# tweeq-IB_Protoboard_v3.net
KiCad netlist of a schematic drawn in EAGLE
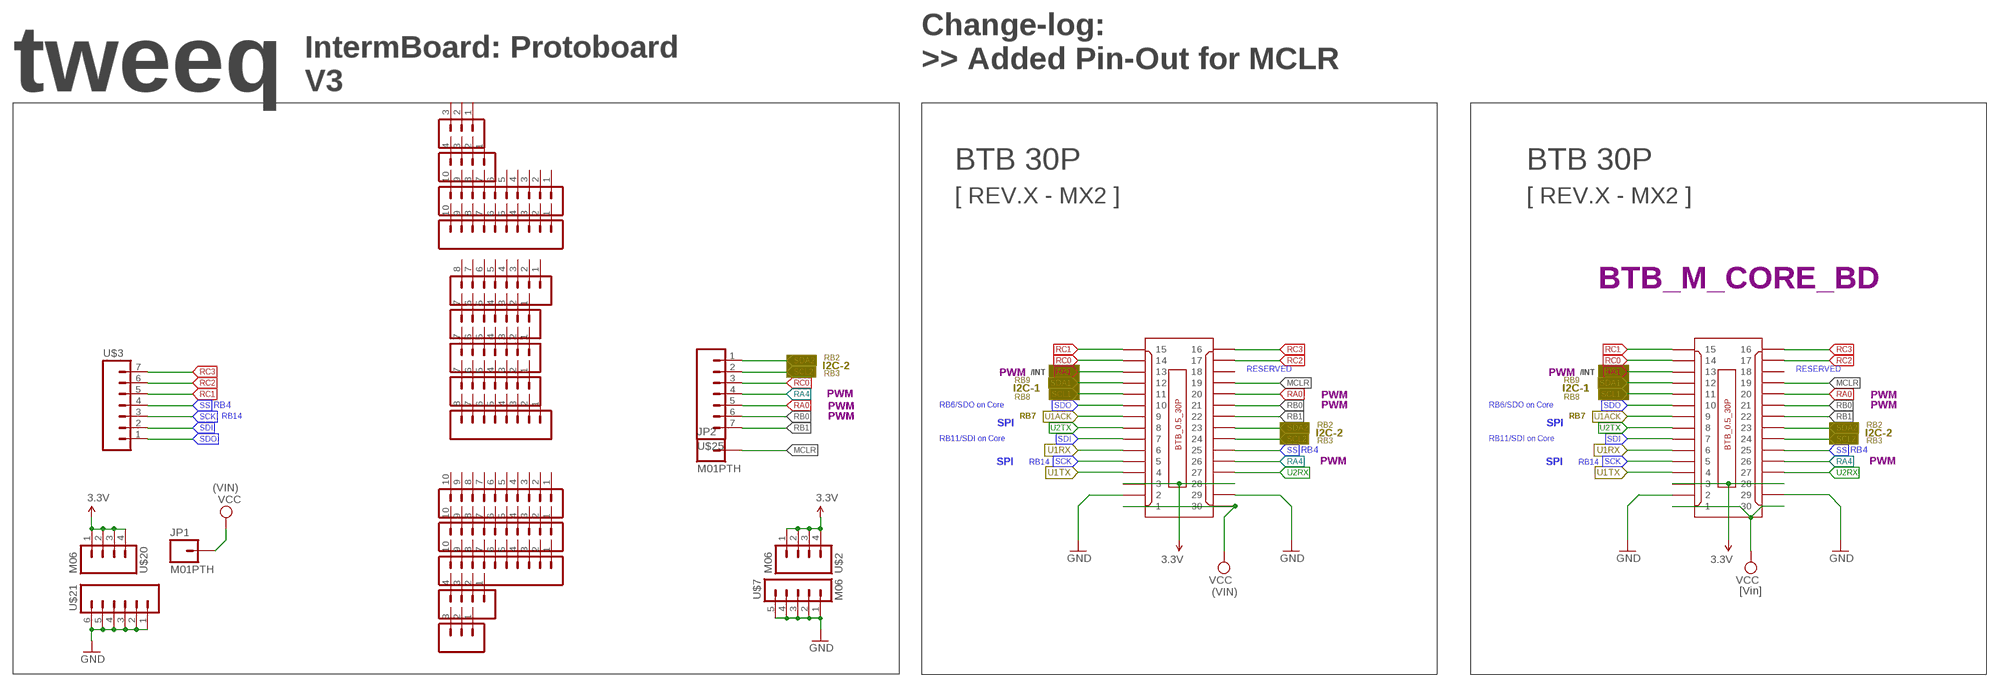
[diagram p0: schematic, sheet 1]

(export (version "E")
  (design (tool "Eeschema 10.0.6"))
  (components
    (comp (ref "JP1")
      (value "M01PTH")
      (footprint "eagle-import:1X01")
      (libsource (lib "eagle-import") (part "M01PTH"))
    )
    (comp (ref "JP2")
      (value "M01PTH")
      (footprint "eagle-import:1X01")
      (libsource (lib "eagle-import") (part "M01PTH"))
    )
    (comp (ref "U$2")
      (value "M06")
      (footprint "eagle-import:1X04_NS_ROUND")
      (libsource (lib "eagle-import") (part "M04NS-CIRC"))
    )
    (comp (ref "U$3")
      (value "M072.54NOSILK")
      (footprint "eagle-import:1X07_NOSILK_")
      (libsource (lib "eagle-import") (part "M072.54NOSILK"))
    )
    (comp (ref "U$4")
      (value "BTB_CONN_30P/F")
      (footprint "eagle-import:BTB0.5-30F-3.0G")
      (libsource (lib "eagle-import") (part "BTB_CONN_30P/F"))
    )
    (comp (ref "U$5")
      (value "M10-1/NS-SQ")
      (footprint "eagle-import:1X03-NS-SQ")
      (libsource (lib "eagle-import") (part "M03NS-SQ"))
    )
    (comp (ref "U$7")
      (value "M06")
      (footprint "eagle-import:1X05-NS-SQ")
      (libsource (lib "eagle-import") (part "M05-1NS-SQ"))
    )
    (comp (ref "U$8")
      (value "M09")
      (footprint "eagle-import:1X10-NS-SQ")
      (libsource (lib "eagle-import") (part "M10-1/NS-SQ"))
    )
    (comp (ref "U$9")
      (value "M09")
      (footprint "eagle-import:1X08-NS-SQ")
      (libsource (lib "eagle-import") (part "M08-1/NS-SQ"))
    )
    (comp (ref "U$10")
      (value "M09")
      (footprint "eagle-import:1X07-NS-SQ")
      (libsource (lib "eagle-import") (part "M07/NS-SQ"))
    )
    (comp (ref "U$11")
      (value "M09")
      (footprint "eagle-import:1X07-NS-SQ")
      (libsource (lib "eagle-import") (part "M07/NS-SQ"))
    )
    (comp (ref "U$12")
      (value "M09")
      (footprint "eagle-import:1X07-NS-SQ")
      (libsource (lib "eagle-import") (part "M07/NS-SQ"))
    )
    (comp (ref "U$13")
      (value "M10-10.1")
      (footprint "eagle-import:1X08-NS-SQ")
      (libsource (lib "eagle-import") (part "M08-1/NS-SQ"))
    )
    (comp (ref "U$14")
      (value "M10-1/NS-SQ")
      (footprint "eagle-import:1X10-NS-SQ")
      (libsource (lib "eagle-import") (part "M10-1/NS-SQ"))
    )
    (comp (ref "U$15")
      (value "M10-1/NS-SQ")
      (footprint "eagle-import:1X10-NS-SQ")
      (libsource (lib "eagle-import") (part "M10-1/NS-SQ"))
    )
    (comp (ref "U$16")
      (value "M10-1/NS-SQ")
      (footprint "eagle-import:1X10-NS-SQ")
      (libsource (lib "eagle-import") (part "M10-1/NS-SQ"))
    )
    (comp (ref "U$17")
      (value "M10-1/NS-SQ")
      (footprint "eagle-import:1X04-NS-SQ")
      (libsource (lib "eagle-import") (part "M04NS-SQ"))
    )
    (comp (ref "U$18")
      (value "M10-1/NS-SQ")
      (footprint "eagle-import:1X10-NS-SQ")
      (libsource (lib "eagle-import") (part "M10-1/NS-SQ"))
    )
    (comp (ref "U$19")
      (value "M10-1/NS-SQ")
      (footprint "eagle-import:1X03-NS-SQ")
      (libsource (lib "eagle-import") (part "M03NS-SQ"))
    )
    (comp (ref "U$20")
      (value "M06")
      (footprint "eagle-import:1X04_NS_ROUND")
      (libsource (lib "eagle-import") (part "M04NS-CIRC"))
    )
    (comp (ref "U$21")
      (value "M06NS-SQ")
      (footprint "eagle-import:1X06-NS-SQ")
      (libsource (lib "eagle-import") (part "M06NS-SQ"))
    )
    (comp (ref "U$22")
      (value "BTB_CONN_30P/M")
      (footprint "eagle-import:BTB0.5-30M-3.0G")
      (libsource (lib "eagle-import") (part "BTB_CONN_30P/M"))
    )
    (comp (ref "U$23")
      (value "M10-1/NS-SQ")
      (footprint "eagle-import:1X04-NS-SQ")
      (libsource (lib "eagle-import") (part "M04NS-SQ"))
    )
    (comp (ref "U$25")
      (value "M072.54NOSILK")
      (footprint "eagle-import:1X07_NOSILK_")
      (libsource (lib "eagle-import") (part "M072.54NOSILK"))
    )
  )
  (nets
    (net (code "1") (name "3.3V") (class "Default")
      (node (ref "U$2") (pin "1") (pinfunction "1_1") (pintype "passive"))
      (node (ref "U$2") (pin "2") (pinfunction "2_2") (pintype "passive"))
      (node (ref "U$2") (pin "3") (pinfunction "3_3") (pintype "passive"))
      (node (ref "U$2") (pin "4") (pinfunction "4_4") (pintype "passive"))
      (node (ref "U$20") (pin "1") (pinfunction "1_1") (pintype "passive"))
      (node (ref "U$20") (pin "2") (pinfunction "2_2") (pintype "passive"))
      (node (ref "U$20") (pin "3") (pinfunction "3_3") (pintype "passive"))
      (node (ref "U$20") (pin "4") (pinfunction "4_4") (pintype "passive"))
      (node (ref "U$22") (pin "28") (pinfunction "28_28") (pintype "bidirectional"))
      (node (ref "U$22") (pin "3") (pinfunction "3_3") (pintype "bidirectional"))
      (node (ref "U$4") (pin "28") (pinfunction "28_28") (pintype "bidirectional"))
      (node (ref "U$4") (pin "3") (pinfunction "3_3") (pintype "bidirectional"))
    )
    (net (code "2") (name "GND") (class "Default")
      (node (ref "U$21") (pin "1") (pinfunction "1_1") (pintype "passive"))
      (node (ref "U$21") (pin "2") (pinfunction "2_2") (pintype "passive"))
      (node (ref "U$21") (pin "3") (pinfunction "3_3") (pintype "passive"))
      (node (ref "U$21") (pin "4") (pinfunction "4_4") (pintype "passive"))
      (node (ref "U$21") (pin "5") (pinfunction "5_5") (pintype "passive"))
      (node (ref "U$21") (pin "6") (pinfunction "6_6") (pintype "passive"))
      (node (ref "U$22") (pin "2") (pinfunction "2_2") (pintype "bidirectional"))
      (node (ref "U$22") (pin "29") (pinfunction "29_29") (pintype "bidirectional"))
      (node (ref "U$4") (pin "2") (pinfunction "2_2") (pintype "bidirectional"))
      (node (ref "U$4") (pin "29") (pinfunction "29_29") (pintype "bidirectional"))
      (node (ref "U$7") (pin "1") (pinfunction "1_1") (pintype "passive"))
      (node (ref "U$7") (pin "2") (pinfunction "2_2") (pintype "passive"))
      (node (ref "U$7") (pin "3") (pinfunction "3_3") (pintype "passive"))
      (node (ref "U$7") (pin "4") (pinfunction "4_4") (pintype "passive"))
      (node (ref "U$7") (pin "5") (pinfunction "5_5") (pintype "passive"))
    )
    (net (code "3") (name "MCLR") (class "Default")
      (node (ref "JP2") (pin "1") (pinfunction "1_1") (pintype "passive"))
      (node (ref "U$22") (pin "19") (pinfunction "19_19") (pintype "bidirectional"))
      (node (ref "U$4") (pin "19") (pinfunction "19_19") (pintype "bidirectional"))
    )
    (net (code "4") (name "RA0") (class "Default")
      (node (ref "U$22") (pin "20") (pinfunction "20_20") (pintype "bidirectional"))
      (node (ref "U$25") (pin "5") (pinfunction "5_5") (pintype "passive"))
      (node (ref "U$4") (pin "20") (pinfunction "20_20") (pintype "bidirectional"))
    )
    (net (code "5") (name "RA1") (class "Default")
      (node (ref "U$22") (pin "13") (pinfunction "13_13") (pintype "bidirectional"))
      (node (ref "U$4") (pin "13") (pinfunction "13_13") (pintype "bidirectional"))
    )
    (net (code "6") (name "RA4") (class "Default")
      (node (ref "U$22") (pin "26") (pinfunction "26_26") (pintype "bidirectional"))
      (node (ref "U$25") (pin "4") (pinfunction "4_4") (pintype "passive"))
      (node (ref "U$4") (pin "26") (pinfunction "26_26") (pintype "bidirectional"))
    )
    (net (code "7") (name "RB0") (class "Default")
      (node (ref "U$22") (pin "21") (pinfunction "21_21") (pintype "bidirectional"))
      (node (ref "U$25") (pin "6") (pinfunction "6_6") (pintype "passive"))
      (node (ref "U$4") (pin "21") (pinfunction "21_21") (pintype "bidirectional"))
    )
    (net (code "8") (name "RB1") (class "Default")
      (node (ref "U$22") (pin "22") (pinfunction "22_22") (pintype "bidirectional"))
      (node (ref "U$25") (pin "7") (pinfunction "7_7") (pintype "passive"))
      (node (ref "U$4") (pin "22") (pinfunction "22_22") (pintype "bidirectional"))
    )
    (net (code "9") (name "RC0") (class "Default")
      (node (ref "U$22") (pin "14") (pinfunction "14_14") (pintype "bidirectional"))
      (node (ref "U$25") (pin "3") (pinfunction "3_3") (pintype "passive"))
      (node (ref "U$4") (pin "14") (pinfunction "14_14") (pintype "bidirectional"))
    )
    (net (code "10") (name "RC1") (class "Default")
      (node (ref "U$22") (pin "15") (pinfunction "15_15") (pintype "bidirectional"))
      (node (ref "U$3") (pin "5") (pinfunction "5_5") (pintype "passive"))
      (node (ref "U$4") (pin "15") (pinfunction "15_15") (pintype "bidirectional"))
    )
    (net (code "11") (name "RC2") (class "Default")
      (node (ref "U$22") (pin "17") (pinfunction "17_17") (pintype "bidirectional"))
      (node (ref "U$3") (pin "6") (pinfunction "6_6") (pintype "passive"))
      (node (ref "U$4") (pin "17") (pinfunction "17_17") (pintype "bidirectional"))
    )
    (net (code "12") (name "RC3") (class "Default")
      (node (ref "U$22") (pin "16") (pinfunction "16_16") (pintype "bidirectional"))
      (node (ref "U$3") (pin "7") (pinfunction "7_7") (pintype "passive"))
      (node (ref "U$4") (pin "16") (pinfunction "16_16") (pintype "bidirectional"))
    )
    (net (code "13") (name "SCK") (class "Default")
      (node (ref "U$22") (pin "5") (pinfunction "5_5") (pintype "bidirectional"))
      (node (ref "U$3") (pin "3") (pinfunction "3_3") (pintype "passive"))
      (node (ref "U$4") (pin "5") (pinfunction "5_5") (pintype "bidirectional"))
    )
    (net (code "14") (name "SCL1") (class "Default")
      (node (ref "U$22") (pin "11") (pinfunction "11_11") (pintype "bidirectional"))
      (node (ref "U$4") (pin "11") (pinfunction "11_11") (pintype "bidirectional"))
    )
    (net (code "15") (name "SCL2") (class "Default")
      (node (ref "U$22") (pin "24") (pinfunction "24_24") (pintype "bidirectional"))
      (node (ref "U$25") (pin "2") (pinfunction "2_2") (pintype "passive"))
      (node (ref "U$4") (pin "24") (pinfunction "24_24") (pintype "bidirectional"))
    )
    (net (code "16") (name "SDA1") (class "Default")
      (node (ref "U$22") (pin "12") (pinfunction "12_12") (pintype "bidirectional"))
      (node (ref "U$4") (pin "12") (pinfunction "12_12") (pintype "bidirectional"))
    )
    (net (code "17") (name "SDA2") (class "Default")
      (node (ref "U$22") (pin "23") (pinfunction "23_23") (pintype "bidirectional"))
      (node (ref "U$25") (pin "1") (pinfunction "1_1") (pintype "passive"))
      (node (ref "U$4") (pin "23") (pinfunction "23_23") (pintype "bidirectional"))
    )
    (net (code "18") (name "SDI") (class "Default")
      (node (ref "U$22") (pin "7") (pinfunction "7_7") (pintype "bidirectional"))
      (node (ref "U$3") (pin "2") (pinfunction "2_2") (pintype "passive"))
      (node (ref "U$4") (pin "7") (pinfunction "7_7") (pintype "bidirectional"))
    )
    (net (code "19") (name "SDO") (class "Default")
      (node (ref "U$22") (pin "10") (pinfunction "10_10") (pintype "bidirectional"))
      (node (ref "U$3") (pin "1") (pinfunction "1_1") (pintype "passive"))
      (node (ref "U$4") (pin "10") (pinfunction "10_10") (pintype "bidirectional"))
    )
    (net (code "20") (name "SS") (class "Default")
      (node (ref "U$22") (pin "25") (pinfunction "25_25") (pintype "bidirectional"))
      (node (ref "U$3") (pin "4") (pinfunction "4_4") (pintype "passive"))
      (node (ref "U$4") (pin "25") (pinfunction "25_25") (pintype "bidirectional"))
    )
    (net (code "21") (name "U1ACK") (class "Default")
      (node (ref "U$22") (pin "9") (pinfunction "9_9") (pintype "bidirectional"))
      (node (ref "U$4") (pin "9") (pinfunction "9_9") (pintype "bidirectional"))
    )
    (net (code "22") (name "U1RX") (class "Default")
      (node (ref "U$22") (pin "6") (pinfunction "6_6") (pintype "bidirectional"))
      (node (ref "U$4") (pin "6") (pinfunction "6_6") (pintype "bidirectional"))
    )
    (net (code "23") (name "U1TX") (class "Default")
      (node (ref "U$22") (pin "4") (pinfunction "4_4") (pintype "bidirectional"))
      (node (ref "U$4") (pin "4") (pinfunction "4_4") (pintype "bidirectional"))
    )
    (net (code "24") (name "U2RX") (class "Default")
      (node (ref "U$22") (pin "27") (pinfunction "27_27") (pintype "bidirectional"))
      (node (ref "U$4") (pin "27") (pinfunction "27_27") (pintype "bidirectional"))
    )
    (net (code "25") (name "U2TX") (class "Default")
      (node (ref "U$22") (pin "8") (pinfunction "8_8") (pintype "bidirectional"))
      (node (ref "U$4") (pin "8") (pinfunction "8_8") (pintype "bidirectional"))
    )
    (net (code "26") (name "VCC") (class "Default")
      (node (ref "JP1") (pin "1") (pinfunction "1_1") (pintype "passive"))
      (node (ref "U$22") (pin "1") (pinfunction "1_1") (pintype "bidirectional"))
      (node (ref "U$22") (pin "30") (pinfunction "30_30") (pintype "bidirectional"))
      (node (ref "U$4") (pin "1") (pinfunction "1_1") (pintype "bidirectional"))
      (node (ref "U$4") (pin "30") (pinfunction "30_30") (pintype "bidirectional"))
    )
    (net (code "27") (name "unconnected-(U$4-Pad18)") (class "Default")
      (node (ref "U$4") (pin "18") (pinfunction "18_18") (pintype "bidirectional"))
    )
    (net (code "28") (name "unconnected-(U$5-Pad1)") (class "Default")
      (node (ref "U$5") (pin "1") (pinfunction "1_1") (pintype "passive"))
    )
    (net (code "29") (name "unconnected-(U$5-Pad2)") (class "Default")
      (node (ref "U$5") (pin "2") (pinfunction "2_2") (pintype "passive"))
    )
    (net (code "30") (name "unconnected-(U$5-Pad3)") (class "Default")
      (node (ref "U$5") (pin "3") (pinfunction "3_3") (pintype "passive"))
    )
    (net (code "31") (name "unconnected-(U$8-Pad1)") (class "Default")
      (node (ref "U$8") (pin "1") (pinfunction "1_1") (pintype "passive"))
    )
    (net (code "32") (name "unconnected-(U$8-Pad2)") (class "Default")
      (node (ref "U$8") (pin "2") (pinfunction "2_2") (pintype "passive"))
    )
    (net (code "33") (name "unconnected-(U$8-Pad3)") (class "Default")
      (node (ref "U$8") (pin "3") (pinfunction "3_3") (pintype "passive"))
    )
    (net (code "34") (name "unconnected-(U$8-Pad4)") (class "Default")
      (node (ref "U$8") (pin "4") (pinfunction "4_4") (pintype "passive"))
    )
    (net (code "35") (name "unconnected-(U$8-Pad5)") (class "Default")
      (node (ref "U$8") (pin "5") (pinfunction "5_5") (pintype "passive"))
    )
    (net (code "36") (name "unconnected-(U$8-Pad6)") (class "Default")
      (node (ref "U$8") (pin "6") (pinfunction "6_6") (pintype "passive"))
    )
    (net (code "37") (name "unconnected-(U$8-Pad7)") (class "Default")
      (node (ref "U$8") (pin "7") (pinfunction "7_7") (pintype "passive"))
    )
    (net (code "38") (name "unconnected-(U$8-Pad8)") (class "Default")
      (node (ref "U$8") (pin "8") (pinfunction "8_8") (pintype "passive"))
    )
    (net (code "39") (name "unconnected-(U$8-Pad9)") (class "Default")
      (node (ref "U$8") (pin "9") (pinfunction "9_9") (pintype "passive"))
    )
    (net (code "40") (name "unconnected-(U$8-Pad10)") (class "Default")
      (node (ref "U$8") (pin "10") (pinfunction "10_10") (pintype "passive"))
    )
    (net (code "41") (name "unconnected-(U$9-Pad1)") (class "Default")
      (node (ref "U$9") (pin "1") (pinfunction "1_1") (pintype "passive"))
    )
    (net (code "42") (name "unconnected-(U$9-Pad2)") (class "Default")
      (node (ref "U$9") (pin "2") (pinfunction "2_2") (pintype "passive"))
    )
    (net (code "43") (name "unconnected-(U$9-Pad3)") (class "Default")
      (node (ref "U$9") (pin "3") (pinfunction "3_3") (pintype "passive"))
    )
    (net (code "44") (name "unconnected-(U$9-Pad4)") (class "Default")
      (node (ref "U$9") (pin "4") (pinfunction "4_4") (pintype "passive"))
    )
    (net (code "45") (name "unconnected-(U$9-Pad5)") (class "Default")
      (node (ref "U$9") (pin "5") (pinfunction "5_5") (pintype "passive"))
    )
    (net (code "46") (name "unconnected-(U$9-Pad6)") (class "Default")
      (node (ref "U$9") (pin "6") (pinfunction "6_6") (pintype "passive"))
    )
    (net (code "47") (name "unconnected-(U$9-Pad7)") (class "Default")
      (node (ref "U$9") (pin "7") (pinfunction "7_7") (pintype "passive"))
    )
    (net (code "48") (name "unconnected-(U$9-Pad8)") (class "Default")
      (node (ref "U$9") (pin "8") (pinfunction "8_8") (pintype "passive"))
    )
    (net (code "49") (name "unconnected-(U$10-Pad1)") (class "Default")
      (node (ref "U$10") (pin "1") (pinfunction "1_1") (pintype "passive"))
    )
    (net (code "50") (name "unconnected-(U$10-Pad2)") (class "Default")
      (node (ref "U$10") (pin "2") (pinfunction "2_2") (pintype "passive"))
    )
    (net (code "51") (name "unconnected-(U$10-Pad3)") (class "Default")
      (node (ref "U$10") (pin "3") (pinfunction "3_3") (pintype "passive"))
    )
    (net (code "52") (name "unconnected-(U$10-Pad4)") (class "Default")
      (node (ref "U$10") (pin "4") (pinfunction "4_4") (pintype "passive"))
    )
    (net (code "53") (name "unconnected-(U$10-Pad5)") (class "Default")
      (node (ref "U$10") (pin "5") (pinfunction "5_5") (pintype "passive"))
    )
    (net (code "54") (name "unconnected-(U$10-Pad6)") (class "Default")
      (node (ref "U$10") (pin "6") (pinfunction "6_6") (pintype "passive"))
    )
    (net (code "55") (name "unconnected-(U$10-Pad7)") (class "Default")
      (node (ref "U$10") (pin "7") (pinfunction "7_7") (pintype "passive"))
    )
    (net (code "56") (name "unconnected-(U$11-Pad1)") (class "Default")
      (node (ref "U$11") (pin "1") (pinfunction "1_1") (pintype "passive"))
    )
    (net (code "57") (name "unconnected-(U$11-Pad2)") (class "Default")
      (node (ref "U$11") (pin "2") (pinfunction "2_2") (pintype "passive"))
    )
    (net (code "58") (name "unconnected-(U$11-Pad3)") (class "Default")
      (node (ref "U$11") (pin "3") (pinfunction "3_3") (pintype "passive"))
    )
    (net (code "59") (name "unconnected-(U$11-Pad4)") (class "Default")
      (node (ref "U$11") (pin "4") (pinfunction "4_4") (pintype "passive"))
    )
    (net (code "60") (name "unconnected-(U$11-Pad5)") (class "Default")
      (node (ref "U$11") (pin "5") (pinfunction "5_5") (pintype "passive"))
    )
    (net (code "61") (name "unconnected-(U$11-Pad6)") (class "Default")
      (node (ref "U$11") (pin "6") (pinfunction "6_6") (pintype "passive"))
    )
    (net (code "62") (name "unconnected-(U$11-Pad7)") (class "Default")
      (node (ref "U$11") (pin "7") (pinfunction "7_7") (pintype "passive"))
    )
    (net (code "63") (name "unconnected-(U$12-Pad1)") (class "Default")
      (node (ref "U$12") (pin "1") (pinfunction "1_1") (pintype "passive"))
    )
    (net (code "64") (name "unconnected-(U$12-Pad2)") (class "Default")
      (node (ref "U$12") (pin "2") (pinfunction "2_2") (pintype "passive"))
    )
    (net (code "65") (name "unconnected-(U$12-Pad3)") (class "Default")
      (node (ref "U$12") (pin "3") (pinfunction "3_3") (pintype "passive"))
    )
    (net (code "66") (name "unconnected-(U$12-Pad4)") (class "Default")
      (node (ref "U$12") (pin "4") (pinfunction "4_4") (pintype "passive"))
    )
    (net (code "67") (name "unconnected-(U$12-Pad5)") (class "Default")
      (node (ref "U$12") (pin "5") (pinfunction "5_5") (pintype "passive"))
    )
    (net (code "68") (name "unconnected-(U$12-Pad6)") (class "Default")
      (node (ref "U$12") (pin "6") (pinfunction "6_6") (pintype "passive"))
    )
    (net (code "69") (name "unconnected-(U$12-Pad7)") (class "Default")
      (node (ref "U$12") (pin "7") (pinfunction "7_7") (pintype "passive"))
    )
    (net (code "70") (name "unconnected-(U$13-Pad1)") (class "Default")
      (node (ref "U$13") (pin "1") (pinfunction "1_1") (pintype "passive"))
    )
    (net (code "71") (name "unconnected-(U$13-Pad2)") (class "Default")
      (node (ref "U$13") (pin "2") (pinfunction "2_2") (pintype "passive"))
    )
    (net (code "72") (name "unconnected-(U$13-Pad3)") (class "Default")
      (node (ref "U$13") (pin "3") (pinfunction "3_3") (pintype "passive"))
    )
    (net (code "73") (name "unconnected-(U$13-Pad4)") (class "Default")
      (node (ref "U$13") (pin "4") (pinfunction "4_4") (pintype "passive"))
    )
    (net (code "74") (name "unconnected-(U$13-Pad5)") (class "Default")
      (node (ref "U$13") (pin "5") (pinfunction "5_5") (pintype "passive"))
    )
    (net (code "75") (name "unconnected-(U$13-Pad6)") (class "Default")
      (node (ref "U$13") (pin "6") (pinfunction "6_6") (pintype "passive"))
    )
    (net (code "76") (name "unconnected-(U$13-Pad7)") (class "Default")
      (node (ref "U$13") (pin "7") (pinfunction "7_7") (pintype "passive"))
    )
    (net (code "77") (name "unconnected-(U$13-Pad8)") (class "Default")
      (node (ref "U$13") (pin "8") (pinfunction "8_8") (pintype "passive"))
    )
    (net (code "78") (name "unconnected-(U$14-Pad1)") (class "Default")
      (node (ref "U$14") (pin "1") (pinfunction "1_1") (pintype "passive"))
    )
    (net (code "79") (name "unconnected-(U$14-Pad2)") (class "Default")
      (node (ref "U$14") (pin "2") (pinfunction "2_2") (pintype "passive"))
    )
    (net (code "80") (name "unconnected-(U$14-Pad3)") (class "Default")
      (node (ref "U$14") (pin "3") (pinfunction "3_3") (pintype "passive"))
    )
    (net (code "81") (name "unconnected-(U$14-Pad4)") (class "Default")
      (node (ref "U$14") (pin "4") (pinfunction "4_4") (pintype "passive"))
    )
    (net (code "82") (name "unconnected-(U$14-Pad5)") (class "Default")
      (node (ref "U$14") (pin "5") (pinfunction "5_5") (pintype "passive"))
    )
    (net (code "83") (name "unconnected-(U$14-Pad6)") (class "Default")
      (node (ref "U$14") (pin "6") (pinfunction "6_6") (pintype "passive"))
    )
    (net (code "84") (name "unconnected-(U$14-Pad7)") (class "Default")
      (node (ref "U$14") (pin "7") (pinfunction "7_7") (pintype "passive"))
    )
    (net (code "85") (name "unconnected-(U$14-Pad8)") (class "Default")
      (node (ref "U$14") (pin "8") (pinfunction "8_8") (pintype "passive"))
    )
    (net (code "86") (name "unconnected-(U$14-Pad9)") (class "Default")
      (node (ref "U$14") (pin "9") (pinfunction "9_9") (pintype "passive"))
    )
    (net (code "87") (name "unconnected-(U$14-Pad10)") (class "Default")
      (node (ref "U$14") (pin "10") (pinfunction "10_10") (pintype "passive"))
    )
    (net (code "88") (name "unconnected-(U$15-Pad1)") (class "Default")
      (node (ref "U$15") (pin "1") (pinfunction "1_1") (pintype "passive"))
    )
    (net (code "89") (name "unconnected-(U$15-Pad2)") (class "Default")
      (node (ref "U$15") (pin "2") (pinfunction "2_2") (pintype "passive"))
    )
    (net (code "90") (name "unconnected-(U$15-Pad3)") (class "Default")
      (node (ref "U$15") (pin "3") (pinfunction "3_3") (pintype "passive"))
    )
    (net (code "91") (name "unconnected-(U$15-Pad4)") (class "Default")
      (node (ref "U$15") (pin "4") (pinfunction "4_4") (pintype "passive"))
    )
    (net (code "92") (name "unconnected-(U$15-Pad5)") (class "Default")
      (node (ref "U$15") (pin "5") (pinfunction "5_5") (pintype "passive"))
    )
    (net (code "93") (name "unconnected-(U$15-Pad6)") (class "Default")
      (node (ref "U$15") (pin "6") (pinfunction "6_6") (pintype "passive"))
    )
    (net (code "94") (name "unconnected-(U$15-Pad7)") (class "Default")
      (node (ref "U$15") (pin "7") (pinfunction "7_7") (pintype "passive"))
    )
    (net (code "95") (name "unconnected-(U$15-Pad8)") (class "Default")
      (node (ref "U$15") (pin "8") (pinfunction "8_8") (pintype "passive"))
    )
    (net (code "96") (name "unconnected-(U$15-Pad9)") (class "Default")
      (node (ref "U$15") (pin "9") (pinfunction "9_9") (pintype "passive"))
    )
    (net (code "97") (name "unconnected-(U$15-Pad10)") (class "Default")
      (node (ref "U$15") (pin "10") (pinfunction "10_10") (pintype "passive"))
    )
    (net (code "98") (name "unconnected-(U$16-Pad1)") (class "Default")
      (node (ref "U$16") (pin "1") (pinfunction "1_1") (pintype "passive"))
    )
    (net (code "99") (name "unconnected-(U$16-Pad2)") (class "Default")
      (node (ref "U$16") (pin "2") (pinfunction "2_2") (pintype "passive"))
    )
    (net (code "100") (name "unconnected-(U$16-Pad3)") (class "Default")
      (node (ref "U$16") (pin "3") (pinfunction "3_3") (pintype "passive"))
    )
    (net (code "101") (name "unconnected-(U$16-Pad4)") (class "Default")
      (node (ref "U$16") (pin "4") (pinfunction "4_4") (pintype "passive"))
    )
    (net (code "102") (name "unconnected-(U$16-Pad5)") (class "Default")
      (node (ref "U$16") (pin "5") (pinfunction "5_5") (pintype "passive"))
    )
    (net (code "103") (name "unconnected-(U$16-Pad6)") (class "Default")
      (node (ref "U$16") (pin "6") (pinfunction "6_6") (pintype "passive"))
    )
    (net (code "104") (name "unconnected-(U$16-Pad7)") (class "Default")
      (node (ref "U$16") (pin "7") (pinfunction "7_7") (pintype "passive"))
    )
    (net (code "105") (name "unconnected-(U$16-Pad8)") (class "Default")
      (node (ref "U$16") (pin "8") (pinfunction "8_8") (pintype "passive"))
    )
    (net (code "106") (name "unconnected-(U$16-Pad9)") (class "Default")
      (node (ref "U$16") (pin "9") (pinfunction "9_9") (pintype "passive"))
    )
    (net (code "107") (name "unconnected-(U$16-Pad10)") (class "Default")
      (node (ref "U$16") (pin "10") (pinfunction "10_10") (pintype "passive"))
    )
    (net (code "108") (name "unconnected-(U$17-Pad1)") (class "Default")
      (node (ref "U$17") (pin "1") (pinfunction "1_1") (pintype "passive"))
    )
    (net (code "109") (name "unconnected-(U$17-Pad2)") (class "Default")
      (node (ref "U$17") (pin "2") (pinfunction "2_2") (pintype "passive"))
    )
    (net (code "110") (name "unconnected-(U$17-Pad3)") (class "Default")
      (node (ref "U$17") (pin "3") (pinfunction "3_3") (pintype "passive"))
    )
    (net (code "111") (name "unconnected-(U$17-Pad4)") (class "Default")
      (node (ref "U$17") (pin "4") (pinfunction "4_4") (pintype "passive"))
    )
    (net (code "112") (name "unconnected-(U$18-Pad1)") (class "Default")
      (node (ref "U$18") (pin "1") (pinfunction "1_1") (pintype "passive"))
    )
    (net (code "113") (name "unconnected-(U$18-Pad2)") (class "Default")
      (node (ref "U$18") (pin "2") (pinfunction "2_2") (pintype "passive"))
    )
    (net (code "114") (name "unconnected-(U$18-Pad3)") (class "Default")
      (node (ref "U$18") (pin "3") (pinfunction "3_3") (pintype "passive"))
    )
    (net (code "115") (name "unconnected-(U$18-Pad4)") (class "Default")
      (node (ref "U$18") (pin "4") (pinfunction "4_4") (pintype "passive"))
    )
    (net (code "116") (name "unconnected-(U$18-Pad5)") (class "Default")
      (node (ref "U$18") (pin "5") (pinfunction "5_5") (pintype "passive"))
    )
    (net (code "117") (name "unconnected-(U$18-Pad6)") (class "Default")
      (node (ref "U$18") (pin "6") (pinfunction "6_6") (pintype "passive"))
    )
    (net (code "118") (name "unconnected-(U$18-Pad7)") (class "Default")
      (node (ref "U$18") (pin "7") (pinfunction "7_7") (pintype "passive"))
    )
    (net (code "119") (name "unconnected-(U$18-Pad8)") (class "Default")
      (node (ref "U$18") (pin "8") (pinfunction "8_8") (pintype "passive"))
    )
    (net (code "120") (name "unconnected-(U$18-Pad9)") (class "Default")
      (node (ref "U$18") (pin "9") (pinfunction "9_9") (pintype "passive"))
    )
    (net (code "121") (name "unconnected-(U$18-Pad10)") (class "Default")
      (node (ref "U$18") (pin "10") (pinfunction "10_10") (pintype "passive"))
    )
    (net (code "122") (name "unconnected-(U$19-Pad1)") (class "Default")
      (node (ref "U$19") (pin "1") (pinfunction "1_1") (pintype "passive"))
    )
    (net (code "123") (name "unconnected-(U$19-Pad2)") (class "Default")
      (node (ref "U$19") (pin "2") (pinfunction "2_2") (pintype "passive"))
    )
    (net (code "124") (name "unconnected-(U$19-Pad3)") (class "Default")
      (node (ref "U$19") (pin "3") (pinfunction "3_3") (pintype "passive"))
    )
    (net (code "125") (name "unconnected-(U$22-Pad18)") (class "Default")
      (node (ref "U$22") (pin "18") (pinfunction "18_18") (pintype "bidirectional"))
    )
    (net (code "126") (name "unconnected-(U$23-Pad1)") (class "Default")
      (node (ref "U$23") (pin "1") (pinfunction "1_1") (pintype "passive"))
    )
    (net (code "127") (name "unconnected-(U$23-Pad2)") (class "Default")
      (node (ref "U$23") (pin "2") (pinfunction "2_2") (pintype "passive"))
    )
    (net (code "128") (name "unconnected-(U$23-Pad3)") (class "Default")
      (node (ref "U$23") (pin "3") (pinfunction "3_3") (pintype "passive"))
    )
    (net (code "129") (name "unconnected-(U$23-Pad4)") (class "Default")
      (node (ref "U$23") (pin "4") (pinfunction "4_4") (pintype "passive"))
    )
  )
)
